# TestRig1a.net
KiCad netlist of a schematic drawn in EAGLE
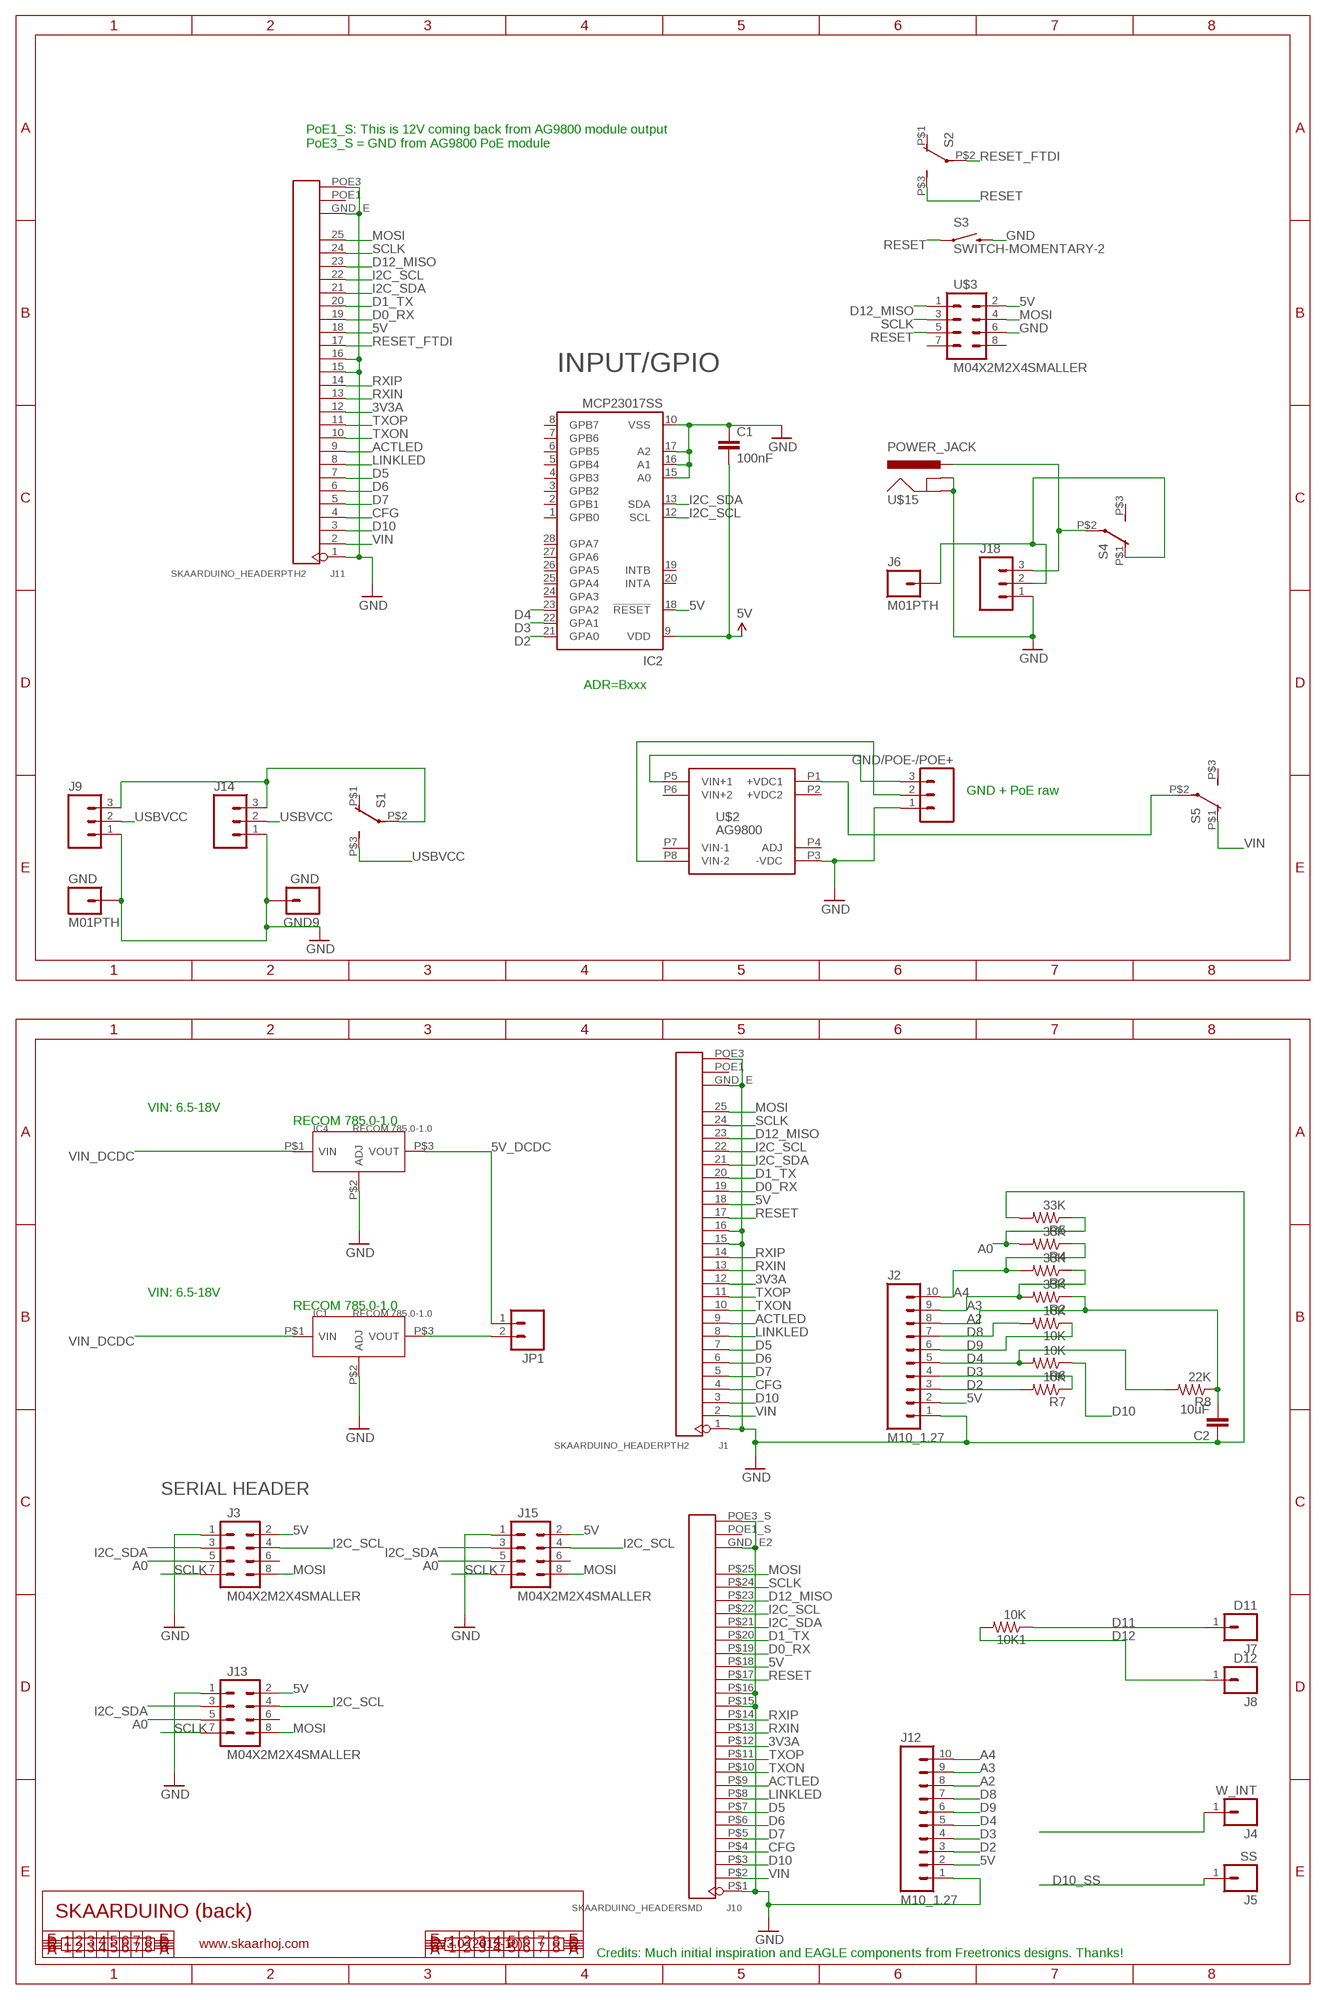
[diagram p0: schematic, sheet 1]

(export (version "E")
  (design (tool "Eeschema 10.0.6"))
  (components
    (comp (ref "10K")
      (value "10K")
      (footprint "eagle-import:0603-RES")
      (libsource (lib "eagle-import") (part "RESISTOR0603-RES"))
    )
    (comp (ref "10K1")
      (value "10K")
      (footprint "eagle-import:0603-RES")
      (libsource (lib "eagle-import") (part "RESISTOR0603-RES"))
    )
    (comp (ref "C1")
      (value "100nF")
      (footprint "eagle-import:0603-CAP")
      (libsource (lib "eagle-import") (part "CAP0603-CAP"))
    )
    (comp (ref "C2")
      (value "10uF")
      (footprint "eagle-import:0805")
      (libsource (lib "eagle-import") (part "CAP0805"))
    )
    (comp (ref "GND")
      (value "M01PTH")
      (footprint "eagle-import:1X01")
      (libsource (lib "eagle-import") (part "M01PTH"))
    )
    (comp (ref "GND/POE-/POE+")
      (value "M03LOCK")
      (footprint "eagle-import:1X03_LOCK")
      (libsource (lib "eagle-import") (part "M03LOCK"))
    )
    (comp (ref "GND9")
      (value "GND")
      (footprint "eagle-import:1X01")
      (libsource (lib "eagle-import") (part "M01PTH"))
    )
    (comp (ref "IC1")
      (value "RECOM 785.0-1.0")
      (footprint "eagle-import:RECOM_785.0-1.0")
      (libsource (lib "eagle-import") (part "PMIC-LM317EMP"))
    )
    (comp (ref "IC2")
      (value "MCP23017SS")
      (footprint "eagle-import:SSOP28")
      (fields
        (field (name "MF") "MICROCHIP")
        (field (name "MPN") "MCP23017-E/SS")
        (field (name "MPN_1") "MCP23017-E/SS")
        (field (name "OC_FARNELL") "1467674")
        (field (name "OC_NEWARK") "31K2960")
      )
      (libsource (lib "eagle-import") (part "MCP23017SS"))
    )
    (comp (ref "IC4")
      (value "RECOM 785.0-1.0")
      (footprint "eagle-import:RECOM_785.0-1.0")
      (libsource (lib "eagle-import") (part "PMIC-LM317EMP"))
    )
    (comp (ref "J1")
      (value "SKAARDUINO_HEADERPTH2")
      (footprint "eagle-import:SKAARDUINO_PTH_HEADER2")
      (libsource (lib "eagle-import") (part "SKAARDUINO_HEADERPTH2"))
    )
    (comp (ref "J2")
      (value "M10_1.27")
      (footprint "eagle-import:M10X1")
      (libsource (lib "eagle-import") (part "M10_1.27"))
    )
    (comp (ref "J3")
      (value "M04X2M2X4SMALLER")
      (footprint "eagle-import:M2X4SMALLER")
      (libsource (lib "eagle-import") (part "M04X2M2X4SMALLER"))
    )
    (comp (ref "J4")
      (value "W_INT")
      (footprint "eagle-import:M1X1")
      (libsource (lib "eagle-import") (part "M1X1TEST"))
    )
    (comp (ref "J5")
      (value "SS")
      (footprint "eagle-import:M1X1")
      (libsource (lib "eagle-import") (part "M1X1TEST"))
    )
    (comp (ref "J6")
      (value "M01PTH")
      (footprint "eagle-import:1X01")
      (libsource (lib "eagle-import") (part "M01PTH"))
    )
    (comp (ref "J7")
      (value "D11")
      (footprint "eagle-import:M1X1")
      (libsource (lib "eagle-import") (part "M1X1TEST"))
    )
    (comp (ref "J8")
      (value "D12")
      (footprint "eagle-import:M1X1")
      (libsource (lib "eagle-import") (part "M1X1TEST"))
    )
    (comp (ref "J9")
      (value "M03LOCK")
      (footprint "eagle-import:1X03_LOCK")
      (libsource (lib "eagle-import") (part "M03LOCK"))
    )
    (comp (ref "J10")
      (value "SKAARDUINO_HEADERSMD")
      (footprint "eagle-import:SKAARDUINO_SMD_HEADER")
      (libsource (lib "eagle-import") (part "SKAARDUINO_HEADERSMD"))
    )
    (comp (ref "J11")
      (value "SKAARDUINO_HEADERPTH2")
      (footprint "eagle-import:SKAARDUINO_PTH_HEADER2")
      (libsource (lib "eagle-import") (part "SKAARDUINO_HEADERPTH2"))
    )
    (comp (ref "J12")
      (value "M10_1.27")
      (footprint "eagle-import:M10X1")
      (libsource (lib "eagle-import") (part "M10_1.27"))
    )
    (comp (ref "J13")
      (value "M04X2M2X4SMALLER")
      (footprint "eagle-import:M2X4SMALLER")
      (libsource (lib "eagle-import") (part "M04X2M2X4SMALLER"))
    )
    (comp (ref "J14")
      (value "M03LOCK")
      (footprint "eagle-import:1X03_LOCK")
      (libsource (lib "eagle-import") (part "M03LOCK"))
    )
    (comp (ref "J15")
      (value "M04X2M2X4SMALLER")
      (footprint "eagle-import:M2X4SMALLER")
      (libsource (lib "eagle-import") (part "M04X2M2X4SMALLER"))
    )
    (comp (ref "J18")
      (value "M03LOCK")
      (footprint "eagle-import:1X03_LOCK")
      (libsource (lib "eagle-import") (part "M03LOCK"))
    )
    (comp (ref "JP1")
      (value "M02PTH")
      (footprint "eagle-import:1X02")
      (libsource (lib "eagle-import") (part "M02PTH"))
    )
    (comp (ref "R2")
      (value "33K")
      (footprint "eagle-import:0603-RES")
      (libsource (lib "eagle-import") (part "RESISTOR0603-RES"))
    )
    (comp (ref "R3")
      (value "33K")
      (footprint "eagle-import:0603-RES")
      (libsource (lib "eagle-import") (part "RESISTOR0603-RES"))
    )
    (comp (ref "R4")
      (value "33K")
      (footprint "eagle-import:0603-RES")
      (libsource (lib "eagle-import") (part "RESISTOR0603-RES"))
    )
    (comp (ref "R5")
      (value "33K")
      (footprint "eagle-import:0603-RES")
      (libsource (lib "eagle-import") (part "RESISTOR0603-RES"))
    )
    (comp (ref "R6")
      (value "10K")
      (footprint "eagle-import:0603-RES")
      (libsource (lib "eagle-import") (part "RESISTOR0603-RES"))
    )
    (comp (ref "R7")
      (value "10K")
      (footprint "eagle-import:0603-RES")
      (libsource (lib "eagle-import") (part "RESISTOR0603-RES"))
    )
    (comp (ref "R8")
      (value "22K")
      (footprint "eagle-import:0603-RES")
      (libsource (lib "eagle-import") (part "RESISTOR0603-RES"))
    )
    (comp (ref "S1")
      (value "SWITCH-DPST")
      (footprint "eagle-import:TECONNECTIVITY-DPST")
      (libsource (lib "eagle-import") (part "SWITCH-DPST"))
    )
    (comp (ref "S2")
      (value "SWITCH-DPST")
      (footprint "eagle-import:TECONNECTIVITY-DPST")
      (libsource (lib "eagle-import") (part "SWITCH-DPST"))
    )
    (comp (ref "S3")
      (value "SWITCH-MOMENTARY-2")
      (footprint "eagle-import:TACTILE_SWITCH_TALL")
      (libsource (lib "eagle-import") (part "SWITCH-MOMENTARY-2"))
    )
    (comp (ref "S4")
      (value "SWITCH-DPST")
      (footprint "eagle-import:TECONNECTIVITY-DPST")
      (libsource (lib "eagle-import") (part "SWITCH-DPST"))
    )
    (comp (ref "S5")
      (value "SWITCH-DPST")
      (footprint "eagle-import:TECONNECTIVITY-DPST")
      (libsource (lib "eagle-import") (part "SWITCH-DPST"))
    )
    (comp (ref "U$2")
      (value "AG9800")
      (footprint "eagle-import:AG9800")
      (libsource (lib "eagle-import") (part "AG9800"))
    )
    (comp (ref "U$3")
      (value "M04X2M2X4SMALLER")
      (footprint "eagle-import:M2X4SMALLER")
      (libsource (lib "eagle-import") (part "M04X2M2X4SMALLER"))
    )
    (comp (ref "U$15")
      (value "POWER_JACK")
      (footprint "eagle-import:POWER_JACK_SMD")
      (libsource (lib "eagle-import") (part "POWER_JACK"))
    )
  )
  (nets
    (net (code "1") (name "3V3A") (class "Default")
      (node (ref "J1") (pin "12") (pinfunction "12_12") (pintype "bidirectional"))
      (node (ref "J10") (pin "P$12") (pinfunction "12_P$12") (pintype "bidirectional"))
      (node (ref "J11") (pin "12") (pinfunction "12_12") (pintype "bidirectional"))
    )
    (net (code "2") (name "5V") (class "Default")
      (node (ref "C1") (pin "2") (pinfunction "2_2") (pintype "passive"))
      (node (ref "IC2") (pin "18") (pinfunction "~{RESET}_18") (pintype "input"))
      (node (ref "IC2") (pin "9") (pinfunction "VDD_9") (pintype "power_in"))
      (node (ref "J1") (pin "18") (pinfunction "18_18") (pintype "bidirectional"))
      (node (ref "J10") (pin "P$18") (pinfunction "18_P$18") (pintype "bidirectional"))
      (node (ref "J11") (pin "18") (pinfunction "18_18") (pintype "bidirectional"))
      (node (ref "J12") (pin "2") (pinfunction "2_2") (pintype "passive"))
      (node (ref "J13") (pin "2") (pinfunction "2_2") (pintype "passive"))
      (node (ref "J15") (pin "2") (pinfunction "2_2") (pintype "passive"))
      (node (ref "J2") (pin "2") (pinfunction "2_2") (pintype "passive"))
      (node (ref "J3") (pin "2") (pinfunction "2_2") (pintype "passive"))
      (node (ref "U$3") (pin "2") (pinfunction "2_2") (pintype "passive"))
    )
    (net (code "3") (name "5V_DCDC") (class "Default")
      (node (ref "IC4") (pin "P$3") (pinfunction "VOUT_P$3") (pintype "bidirectional"))
      (node (ref "JP1") (pin "1") (pinfunction "1_1") (pintype "passive"))
    )
    (net (code "4") (name "A0") (class "Default")
      (node (ref "J13") (pin "5") (pinfunction "5_5") (pintype "passive"))
      (node (ref "J15") (pin "5") (pinfunction "5_5") (pintype "passive"))
      (node (ref "J3") (pin "5") (pinfunction "5_5") (pintype "passive"))
      (node (ref "R4") (pin "2") (pinfunction "2_2") (pintype "passive"))
      (node (ref "R5") (pin "1") (pinfunction "1_1") (pintype "passive"))
    )
    (net (code "5") (name "A2") (class "Default")
      (node (ref "C2") (pin "2") (pinfunction "2_2") (pintype "passive"))
      (node (ref "J12") (pin "8") (pinfunction "8_8") (pintype "passive"))
      (node (ref "J2") (pin "8") (pinfunction "8_8") (pintype "passive"))
      (node (ref "R2") (pin "1") (pinfunction "1_1") (pintype "passive"))
      (node (ref "R8") (pin "1") (pinfunction "1_1") (pintype "passive"))
    )
    (net (code "6") (name "A3") (class "Default")
      (node (ref "J12") (pin "9") (pinfunction "9_9") (pintype "passive"))
      (node (ref "J2") (pin "9") (pinfunction "9_9") (pintype "passive"))
      (node (ref "R2") (pin "2") (pinfunction "2_2") (pintype "passive"))
      (node (ref "R3") (pin "1") (pinfunction "1_1") (pintype "passive"))
    )
    (net (code "7") (name "A4") (class "Default")
      (node (ref "J12") (pin "10") (pinfunction "10_10") (pintype "passive"))
      (node (ref "J2") (pin "10") (pinfunction "10_10") (pintype "passive"))
      (node (ref "R3") (pin "2") (pinfunction "2_2") (pintype "passive"))
      (node (ref "R4") (pin "1") (pinfunction "1_1") (pintype "passive"))
    )
    (net (code "8") (name "ACTLED") (class "Default")
      (node (ref "J1") (pin "9") (pinfunction "9_9") (pintype "bidirectional"))
      (node (ref "J10") (pin "P$9") (pinfunction "9_P$9") (pintype "bidirectional"))
      (node (ref "J11") (pin "9") (pinfunction "9_9") (pintype "bidirectional"))
    )
    (net (code "9") (name "CFG") (class "Default")
      (node (ref "J1") (pin "4") (pinfunction "4_4") (pintype "bidirectional"))
      (node (ref "J10") (pin "P$4") (pinfunction "4_P$4") (pintype "bidirectional"))
      (node (ref "J11") (pin "4") (pinfunction "4_4") (pintype "bidirectional"))
    )
    (net (code "10") (name "D0_RX") (class "Default")
      (node (ref "J1") (pin "19") (pinfunction "19_19") (pintype "bidirectional"))
      (node (ref "J10") (pin "P$19") (pinfunction "19_P$19") (pintype "bidirectional"))
      (node (ref "J11") (pin "19") (pinfunction "19_19") (pintype "bidirectional"))
    )
    (net (code "11") (name "D1_TX") (class "Default")
      (node (ref "J1") (pin "20") (pinfunction "20_20") (pintype "bidirectional"))
      (node (ref "J10") (pin "P$20") (pinfunction "20_P$20") (pintype "bidirectional"))
      (node (ref "J11") (pin "20") (pinfunction "20_20") (pintype "bidirectional"))
    )
    (net (code "12") (name "D2") (class "Default")
      (node (ref "IC2") (pin "21") (pinfunction "GPA0_21") (pintype "bidirectional"))
      (node (ref "J12") (pin "3") (pinfunction "3_3") (pintype "passive"))
      (node (ref "J2") (pin "3") (pinfunction "3_3") (pintype "passive"))
      (node (ref "R7") (pin "2") (pinfunction "2_2") (pintype "passive"))
    )
    (net (code "13") (name "D3") (class "Default")
      (node (ref "IC2") (pin "22") (pinfunction "GPA1_22") (pintype "bidirectional"))
      (node (ref "J12") (pin "4") (pinfunction "4_4") (pintype "passive"))
      (node (ref "J2") (pin "4") (pinfunction "4_4") (pintype "passive"))
      (node (ref "R7") (pin "1") (pinfunction "1_1") (pintype "passive"))
    )
    (net (code "14") (name "D4") (class "Default")
      (node (ref "IC2") (pin "23") (pinfunction "GPA2_23") (pintype "bidirectional"))
      (node (ref "J12") (pin "5") (pinfunction "5_5") (pintype "passive"))
      (node (ref "J2") (pin "5") (pinfunction "5_5") (pintype "passive"))
      (node (ref "R6") (pin "2") (pinfunction "2_2") (pintype "passive"))
      (node (ref "R8") (pin "2") (pinfunction "2_2") (pintype "passive"))
    )
    (net (code "15") (name "D5") (class "Default")
      (node (ref "J1") (pin "7") (pinfunction "7_7") (pintype "bidirectional"))
      (node (ref "J10") (pin "P$7") (pinfunction "7_P$7") (pintype "bidirectional"))
      (node (ref "J11") (pin "7") (pinfunction "7_7") (pintype "bidirectional"))
    )
    (net (code "16") (name "D6") (class "Default")
      (node (ref "J1") (pin "6") (pinfunction "6_6") (pintype "bidirectional"))
      (node (ref "J10") (pin "P$6") (pinfunction "6_P$6") (pintype "bidirectional"))
      (node (ref "J11") (pin "6") (pinfunction "6_6") (pintype "bidirectional"))
    )
    (net (code "17") (name "D7") (class "Default")
      (node (ref "J1") (pin "5") (pinfunction "5_5") (pintype "bidirectional"))
      (node (ref "J10") (pin "P$5") (pinfunction "5_P$5") (pintype "bidirectional"))
      (node (ref "J11") (pin "5") (pinfunction "5_5") (pintype "bidirectional"))
    )
    (net (code "18") (name "D8") (class "Default")
      (node (ref "10K") (pin "2") (pinfunction "2_2") (pintype "passive"))
      (node (ref "J12") (pin "7") (pinfunction "7_7") (pintype "passive"))
      (node (ref "J2") (pin "7") (pinfunction "7_7") (pintype "passive"))
    )
    (net (code "19") (name "D9") (class "Default")
      (node (ref "10K") (pin "1") (pinfunction "1_1") (pintype "passive"))
      (node (ref "J12") (pin "6") (pinfunction "6_6") (pintype "passive"))
      (node (ref "J2") (pin "6") (pinfunction "6_6") (pintype "passive"))
    )
    (net (code "20") (name "D10") (class "Default")
      (node (ref "J1") (pin "3") (pinfunction "3_3") (pintype "bidirectional"))
      (node (ref "J10") (pin "P$3") (pinfunction "3_P$3") (pintype "bidirectional"))
      (node (ref "J11") (pin "3") (pinfunction "3_3") (pintype "bidirectional"))
      (node (ref "R6") (pin "1") (pinfunction "1_1") (pintype "passive"))
    )
    (net (code "21") (name "D10_SS") (class "Default")
      (node (ref "J5") (pin "1") (pinfunction "5_1") (pintype "passive"))
    )
    (net (code "22") (name "D11") (class "Default")
      (node (ref "10K1") (pin "1") (pinfunction "1_1") (pintype "passive"))
      (node (ref "J7") (pin "1") (pinfunction "5_1") (pintype "passive"))
    )
    (net (code "23") (name "D12") (class "Default")
      (node (ref "10K1") (pin "2") (pinfunction "2_2") (pintype "passive"))
      (node (ref "J8") (pin "1") (pinfunction "5_1") (pintype "passive"))
    )
    (net (code "24") (name "D12_MISO") (class "Default")
      (node (ref "J1") (pin "23") (pinfunction "23_23") (pintype "bidirectional"))
      (node (ref "J10") (pin "P$23") (pinfunction "23_P$23") (pintype "bidirectional"))
      (node (ref "J11") (pin "23") (pinfunction "23_23") (pintype "bidirectional"))
      (node (ref "U$3") (pin "1") (pinfunction "1_1") (pintype "passive"))
    )
    (net (code "25") (name "GND") (class "Default")
      (node (ref "C1") (pin "1") (pinfunction "1_1") (pintype "passive"))
      (node (ref "C2") (pin "1") (pinfunction "1_1") (pintype "passive"))
      (node (ref "GND") (pin "1") (pinfunction "1_1") (pintype "passive"))
      (node (ref "GND/POE-/POE+") (pin "1") (pinfunction "1_1") (pintype "passive"))
      (node (ref "GND9") (pin "1") (pinfunction "1_1") (pintype "passive"))
      (node (ref "IC1") (pin "P$2") (pinfunction "ADJ_P$2") (pintype "bidirectional"))
      (node (ref "IC2") (pin "10") (pinfunction "VSS_10") (pintype "power_in"))
      (node (ref "IC2") (pin "15") (pinfunction "A0_15") (pintype "input"))
      (node (ref "IC2") (pin "16") (pinfunction "A1_16") (pintype "input"))
      (node (ref "IC2") (pin "17") (pinfunction "A2_17") (pintype "input"))
      (node (ref "IC4") (pin "P$2") (pinfunction "ADJ_P$2") (pintype "bidirectional"))
      (node (ref "J1") (pin "1") (pinfunction "1_1") (pintype "bidirectional"))
      (node (ref "J1") (pin "15") (pinfunction "15_15") (pintype "bidirectional"))
      (node (ref "J1") (pin "16") (pinfunction "16_16") (pintype "bidirectional"))
      (node (ref "J1") (pin "GND_E") (pinfunction "26_GND_E") (pintype "bidirectional"))
      (node (ref "J1") (pin "POE3") (pinfunction "28_POE3") (pintype "bidirectional"))
      (node (ref "J10") (pin "GND_E2") (pinfunction "26_GND_E2") (pintype "bidirectional"))
      (node (ref "J10") (pin "P$1") (pinfunction "1_P$1") (pintype "bidirectional"))
      (node (ref "J10") (pin "P$15") (pinfunction "15_P$15") (pintype "bidirectional"))
      (node (ref "J10") (pin "P$16") (pinfunction "16_P$16") (pintype "bidirectional"))
      (node (ref "J10") (pin "POE3_S") (pinfunction "28_POE3_S") (pintype "bidirectional"))
      (node (ref "J11") (pin "1") (pinfunction "1_1") (pintype "bidirectional"))
      (node (ref "J11") (pin "15") (pinfunction "15_15") (pintype "bidirectional"))
      (node (ref "J11") (pin "16") (pinfunction "16_16") (pintype "bidirectional"))
      (node (ref "J11") (pin "GND_E") (pinfunction "26_GND_E") (pintype "bidirectional"))
      (node (ref "J11") (pin "POE3") (pinfunction "28_POE3") (pintype "bidirectional"))
      (node (ref "J12") (pin "1") (pinfunction "1_1") (pintype "passive"))
      (node (ref "J13") (pin "1") (pinfunction "1_1") (pintype "passive"))
      (node (ref "J14") (pin "1") (pinfunction "1_1") (pintype "passive"))
      (node (ref "J15") (pin "1") (pinfunction "1_1") (pintype "passive"))
      (node (ref "J18") (pin "1") (pinfunction "1_1") (pintype "passive"))
      (node (ref "J2") (pin "1") (pinfunction "1_1") (pintype "passive"))
      (node (ref "J3") (pin "1") (pinfunction "1_1") (pintype "passive"))
      (node (ref "J9") (pin "1") (pinfunction "1_1") (pintype "passive"))
      (node (ref "R5") (pin "2") (pinfunction "2_2") (pintype "passive"))
      (node (ref "S3") (pin "B2") (pinfunction "2_B2") (pintype "passive"))
      (node (ref "U$15") (pin "GND") (pinfunction "GND_GND") (pintype "bidirectional"))
      (node (ref "U$15") (pin "SHUNT") (pinfunction "GNDBREAK_SHUNT") (pintype "bidirectional"))
      (node (ref "U$2") (pin "P3") (pinfunction "-VDC_P3") (pintype "bidirectional"))
      (node (ref "U$3") (pin "6") (pinfunction "6_6") (pintype "passive"))
    )
    (net (code "26") (name "I2C_SCL") (class "Default")
      (node (ref "IC2") (pin "12") (pinfunction "SCL_12") (pintype "input"))
      (node (ref "J1") (pin "22") (pinfunction "22_22") (pintype "bidirectional"))
      (node (ref "J10") (pin "P$22") (pinfunction "22_P$22") (pintype "bidirectional"))
      (node (ref "J11") (pin "22") (pinfunction "22_22") (pintype "bidirectional"))
      (node (ref "J13") (pin "4") (pinfunction "4_4") (pintype "passive"))
      (node (ref "J15") (pin "4") (pinfunction "4_4") (pintype "passive"))
      (node (ref "J3") (pin "4") (pinfunction "4_4") (pintype "passive"))
    )
    (net (code "27") (name "I2C_SDA") (class "Default")
      (node (ref "IC2") (pin "13") (pinfunction "SDA_13") (pintype "bidirectional"))
      (node (ref "J1") (pin "21") (pinfunction "21_21") (pintype "bidirectional"))
      (node (ref "J10") (pin "P$21") (pinfunction "21_P$21") (pintype "bidirectional"))
      (node (ref "J11") (pin "21") (pinfunction "21_21") (pintype "bidirectional"))
      (node (ref "J13") (pin "3") (pinfunction "3_3") (pintype "passive"))
      (node (ref "J15") (pin "3") (pinfunction "3_3") (pintype "passive"))
      (node (ref "J3") (pin "3") (pinfunction "3_3") (pintype "passive"))
    )
    (net (code "28") (name "LINKLED") (class "Default")
      (node (ref "J1") (pin "8") (pinfunction "8_8") (pintype "bidirectional"))
      (node (ref "J10") (pin "P$8") (pinfunction "8_P$8") (pintype "bidirectional"))
      (node (ref "J11") (pin "8") (pinfunction "8_8") (pintype "bidirectional"))
    )
    (net (code "29") (name "MOSI") (class "Default")
      (node (ref "J1") (pin "25") (pinfunction "25_25") (pintype "bidirectional"))
      (node (ref "J10") (pin "P$25") (pinfunction "25_P$25") (pintype "bidirectional"))
      (node (ref "J11") (pin "25") (pinfunction "25_25") (pintype "bidirectional"))
      (node (ref "J13") (pin "8") (pinfunction "8_8") (pintype "passive"))
      (node (ref "J15") (pin "8") (pinfunction "8_8") (pintype "passive"))
      (node (ref "J3") (pin "8") (pinfunction "8_8") (pintype "passive"))
      (node (ref "U$3") (pin "4") (pinfunction "4_4") (pintype "passive"))
    )
    (net (code "30") (name "Net-(IC1-VOUT)") (class "Default")
      (node (ref "IC1") (pin "P$3") (pinfunction "VOUT_P$3") (pintype "bidirectional"))
      (node (ref "JP1") (pin "2") (pinfunction "2_2") (pintype "passive"))
    )
    (net (code "31") (name "Net-(S1-P)") (class "Default")
      (node (ref "J14") (pin "3") (pinfunction "3_3") (pintype "passive"))
      (node (ref "J9") (pin "3") (pinfunction "3_3") (pintype "passive"))
      (node (ref "S1") (pin "P$2") (pinfunction "P_P$2") (pintype "passive"))
    )
    (net (code "32") (name "Net-(S4-O)") (class "Default")
      (node (ref "J18") (pin "2") (pinfunction "2_2") (pintype "passive"))
      (node (ref "J6") (pin "1") (pinfunction "1_1") (pintype "passive"))
      (node (ref "S4") (pin "P$1") (pinfunction "O_P$1") (pintype "passive"))
    )
    (net (code "33") (name "Net-(S4-P)") (class "Default")
      (node (ref "J18") (pin "3") (pinfunction "3_3") (pintype "passive"))
      (node (ref "S4") (pin "P$2") (pinfunction "P_P$2") (pintype "passive"))
      (node (ref "U$15") (pin "PWR") (pinfunction "PWR_PWR") (pintype "bidirectional"))
    )
    (net (code "34") (name "Net-(S5-P)") (class "Default")
      (node (ref "S5") (pin "P$2") (pinfunction "P_P$2") (pintype "passive"))
      (node (ref "U$2") (pin "P1") (pinfunction "+VDC1_P1") (pintype "bidirectional"))
    )
    (net (code "35") (name "Net-(U$2-VIN+1)") (class "Default")
      (node (ref "GND/POE-/POE+") (pin "3") (pinfunction "3_3") (pintype "passive"))
      (node (ref "U$2") (pin "P5") (pinfunction "VIN+1_P5") (pintype "power_in"))
    )
    (net (code "36") (name "Net-(U$2-VIN-2)") (class "Default")
      (node (ref "GND/POE-/POE+") (pin "2") (pinfunction "2_2") (pintype "passive"))
      (node (ref "U$2") (pin "P8") (pinfunction "VIN-2_P8") (pintype "power_in"))
    )
    (net (code "37") (name "RESET") (class "Default")
      (node (ref "J1") (pin "17") (pinfunction "17_17") (pintype "bidirectional"))
      (node (ref "J10") (pin "P$17") (pinfunction "17_P$17") (pintype "bidirectional"))
      (node (ref "S2") (pin "P$3") (pinfunction "S_P$3") (pintype "passive"))
      (node (ref "S3") (pin "A2") (pinfunction "1_A2") (pintype "passive"))
      (node (ref "U$3") (pin "5") (pinfunction "5_5") (pintype "passive"))
    )
    (net (code "38") (name "RESET_FTDI") (class "Default")
      (node (ref "J11") (pin "17") (pinfunction "17_17") (pintype "bidirectional"))
      (node (ref "S2") (pin "P$2") (pinfunction "P_P$2") (pintype "passive"))
    )
    (net (code "39") (name "RXIN") (class "Default")
      (node (ref "J1") (pin "13") (pinfunction "13_13") (pintype "bidirectional"))
      (node (ref "J10") (pin "P$13") (pinfunction "13_P$13") (pintype "bidirectional"))
      (node (ref "J11") (pin "13") (pinfunction "13_13") (pintype "bidirectional"))
    )
    (net (code "40") (name "RXIP") (class "Default")
      (node (ref "J1") (pin "14") (pinfunction "14_14") (pintype "bidirectional"))
      (node (ref "J10") (pin "P$14") (pinfunction "14_P$14") (pintype "bidirectional"))
      (node (ref "J11") (pin "14") (pinfunction "14_14") (pintype "bidirectional"))
    )
    (net (code "41") (name "SCLK") (class "Default")
      (node (ref "J1") (pin "24") (pinfunction "24_24") (pintype "bidirectional"))
      (node (ref "J10") (pin "P$24") (pinfunction "24_P$24") (pintype "bidirectional"))
      (node (ref "J11") (pin "24") (pinfunction "24_24") (pintype "bidirectional"))
      (node (ref "J13") (pin "7") (pinfunction "7_7") (pintype "passive"))
      (node (ref "J15") (pin "7") (pinfunction "7_7") (pintype "passive"))
      (node (ref "J3") (pin "7") (pinfunction "7_7") (pintype "passive"))
      (node (ref "U$3") (pin "3") (pinfunction "3_3") (pintype "passive"))
    )
    (net (code "42") (name "TXON") (class "Default")
      (node (ref "J1") (pin "10") (pinfunction "10_10") (pintype "bidirectional"))
      (node (ref "J10") (pin "P$10") (pinfunction "10_P$10") (pintype "bidirectional"))
      (node (ref "J11") (pin "10") (pinfunction "10_10") (pintype "bidirectional"))
    )
    (net (code "43") (name "TXOP") (class "Default")
      (node (ref "J1") (pin "11") (pinfunction "11_11") (pintype "bidirectional"))
      (node (ref "J10") (pin "P$11") (pinfunction "11_P$11") (pintype "bidirectional"))
      (node (ref "J11") (pin "11") (pinfunction "11_11") (pintype "bidirectional"))
    )
    (net (code "44") (name "USBVCC") (class "Default")
      (node (ref "J14") (pin "2") (pinfunction "2_2") (pintype "passive"))
      (node (ref "J9") (pin "2") (pinfunction "2_2") (pintype "passive"))
      (node (ref "S1") (pin "P$3") (pinfunction "S_P$3") (pintype "passive"))
    )
    (net (code "45") (name "VIN") (class "Default")
      (node (ref "J1") (pin "2") (pinfunction "2_2") (pintype "bidirectional"))
      (node (ref "J10") (pin "P$2") (pinfunction "2_P$2") (pintype "bidirectional"))
      (node (ref "J11") (pin "2") (pinfunction "2_2") (pintype "bidirectional"))
      (node (ref "S5") (pin "P$1") (pinfunction "O_P$1") (pintype "passive"))
    )
    (net (code "46") (name "VIN+2") (class "Default")
      (node (ref "U$2") (pin "P6") (pinfunction "VIN+2_P6") (pintype "power_in"))
    )
    (net (code "47") (name "VIN-1") (class "Default")
      (node (ref "U$2") (pin "P7") (pinfunction "VIN-1_P7") (pintype "power_in"))
    )
    (net (code "48") (name "VIN_DCDC") (class "Default")
      (node (ref "IC1") (pin "P$1") (pinfunction "VIN_P$1") (pintype "bidirectional"))
      (node (ref "IC4") (pin "P$1") (pinfunction "VIN_P$1") (pintype "bidirectional"))
    )
    (net (code "49") (name "unconnected-(IC2-GPA3-Pad24)") (class "Default")
      (node (ref "IC2") (pin "24") (pinfunction "GPA3_24") (pintype "bidirectional"))
    )
    (net (code "50") (name "unconnected-(IC2-GPA4-Pad25)") (class "Default")
      (node (ref "IC2") (pin "25") (pinfunction "GPA4_25") (pintype "bidirectional"))
    )
    (net (code "51") (name "unconnected-(IC2-GPA5-Pad26)") (class "Default")
      (node (ref "IC2") (pin "26") (pinfunction "GPA5_26") (pintype "bidirectional"))
    )
    (net (code "52") (name "unconnected-(IC2-GPA6-Pad27)") (class "Default")
      (node (ref "IC2") (pin "27") (pinfunction "GPA6_27") (pintype "bidirectional"))
    )
    (net (code "53") (name "unconnected-(IC2-GPA7-Pad28)") (class "Default")
      (node (ref "IC2") (pin "28") (pinfunction "GPA7_28") (pintype "bidirectional"))
    )
    (net (code "54") (name "unconnected-(IC2-GPB0-Pad1)") (class "Default")
      (node (ref "IC2") (pin "1") (pinfunction "GPB0_1") (pintype "bidirectional"))
    )
    (net (code "55") (name "unconnected-(IC2-GPB1-Pad2)") (class "Default")
      (node (ref "IC2") (pin "2") (pinfunction "GPB1_2") (pintype "bidirectional"))
    )
    (net (code "56") (name "unconnected-(IC2-GPB2-Pad3)") (class "Default")
      (node (ref "IC2") (pin "3") (pinfunction "GPB2_3") (pintype "bidirectional"))
    )
    (net (code "57") (name "unconnected-(IC2-GPB3-Pad4)") (class "Default")
      (node (ref "IC2") (pin "4") (pinfunction "GPB3_4") (pintype "bidirectional"))
    )
    (net (code "58") (name "unconnected-(IC2-GPB4-Pad5)") (class "Default")
      (node (ref "IC2") (pin "5") (pinfunction "GPB4_5") (pintype "bidirectional"))
    )
    (net (code "59") (name "unconnected-(IC2-GPB5-Pad6)") (class "Default")
      (node (ref "IC2") (pin "6") (pinfunction "GPB5_6") (pintype "bidirectional"))
    )
    (net (code "60") (name "unconnected-(IC2-GPB6-Pad7)") (class "Default")
      (node (ref "IC2") (pin "7") (pinfunction "GPB6_7") (pintype "bidirectional"))
    )
    (net (code "61") (name "unconnected-(IC2-GPB7-Pad8)") (class "Default")
      (node (ref "IC2") (pin "8") (pinfunction "GPB7_8") (pintype "bidirectional"))
    )
    (net (code "62") (name "unconnected-(IC2-INTA-Pad20)") (class "Default")
      (node (ref "IC2") (pin "20") (pinfunction "INTA_20") (pintype "output"))
    )
    (net (code "63") (name "unconnected-(IC2-INTB-Pad19)") (class "Default")
      (node (ref "IC2") (pin "19") (pinfunction "INTB_19") (pintype "output"))
    )
    (net (code "64") (name "unconnected-(J1-27-PadPOE1)") (class "Default")
      (node (ref "J1") (pin "POE1") (pinfunction "27_POE1") (pintype "bidirectional"))
    )
    (net (code "65") (name "unconnected-(J3-Pad6)") (class "Default")
      (node (ref "J3") (pin "6") (pinfunction "6_6") (pintype "passive"))
    )
    (net (code "66") (name "unconnected-(J4-5-Pad1)") (class "Default")
      (node (ref "J4") (pin "1") (pinfunction "5_1") (pintype "passive"))
    )
    (net (code "67") (name "unconnected-(J10-27-PadPOE1_S)") (class "Default")
      (node (ref "J10") (pin "POE1_S") (pinfunction "27_POE1_S") (pintype "bidirectional"))
    )
    (net (code "68") (name "unconnected-(J11-27-PadPOE1)") (class "Default")
      (node (ref "J11") (pin "POE1") (pinfunction "27_POE1") (pintype "bidirectional"))
    )
    (net (code "69") (name "unconnected-(J13-Pad6)") (class "Default")
      (node (ref "J13") (pin "6") (pinfunction "6_6") (pintype "passive"))
    )
    (net (code "70") (name "unconnected-(J15-Pad6)") (class "Default")
      (node (ref "J15") (pin "6") (pinfunction "6_6") (pintype "passive"))
    )
    (net (code "71") (name "unconnected-(S1-O-PadP$1)") (class "Default")
      (node (ref "S1") (pin "P$1") (pinfunction "O_P$1") (pintype "passive"))
    )
    (net (code "72") (name "unconnected-(S2-O-PadP$1)") (class "Default")
      (node (ref "S2") (pin "P$1") (pinfunction "O_P$1") (pintype "passive"))
    )
    (net (code "73") (name "unconnected-(S4-S-PadP$3)") (class "Default")
      (node (ref "S4") (pin "P$3") (pinfunction "S_P$3") (pintype "passive"))
    )
    (net (code "74") (name "unconnected-(S5-S-PadP$3)") (class "Default")
      (node (ref "S5") (pin "P$3") (pinfunction "S_P$3") (pintype "passive"))
    )
    (net (code "75") (name "unconnected-(U$2-+VDC2-PadP2)") (class "Default")
      (node (ref "U$2") (pin "P2") (pinfunction "+VDC2_P2") (pintype "bidirectional"))
    )
    (net (code "76") (name "unconnected-(U$2-ADJ-PadP4)") (class "Default")
      (node (ref "U$2") (pin "P4") (pinfunction "ADJ_P4") (pintype "input"))
    )
    (net (code "77") (name "unconnected-(U$3-Pad7)") (class "Default")
      (node (ref "U$3") (pin "7") (pinfunction "7_7") (pintype "passive"))
    )
    (net (code "78") (name "unconnected-(U$3-Pad8)") (class "Default")
      (node (ref "U$3") (pin "8") (pinfunction "8_8") (pintype "passive"))
    )
  )
)
